# mixer.net
KiCad netlist of a schematic drawn in Altium Designer
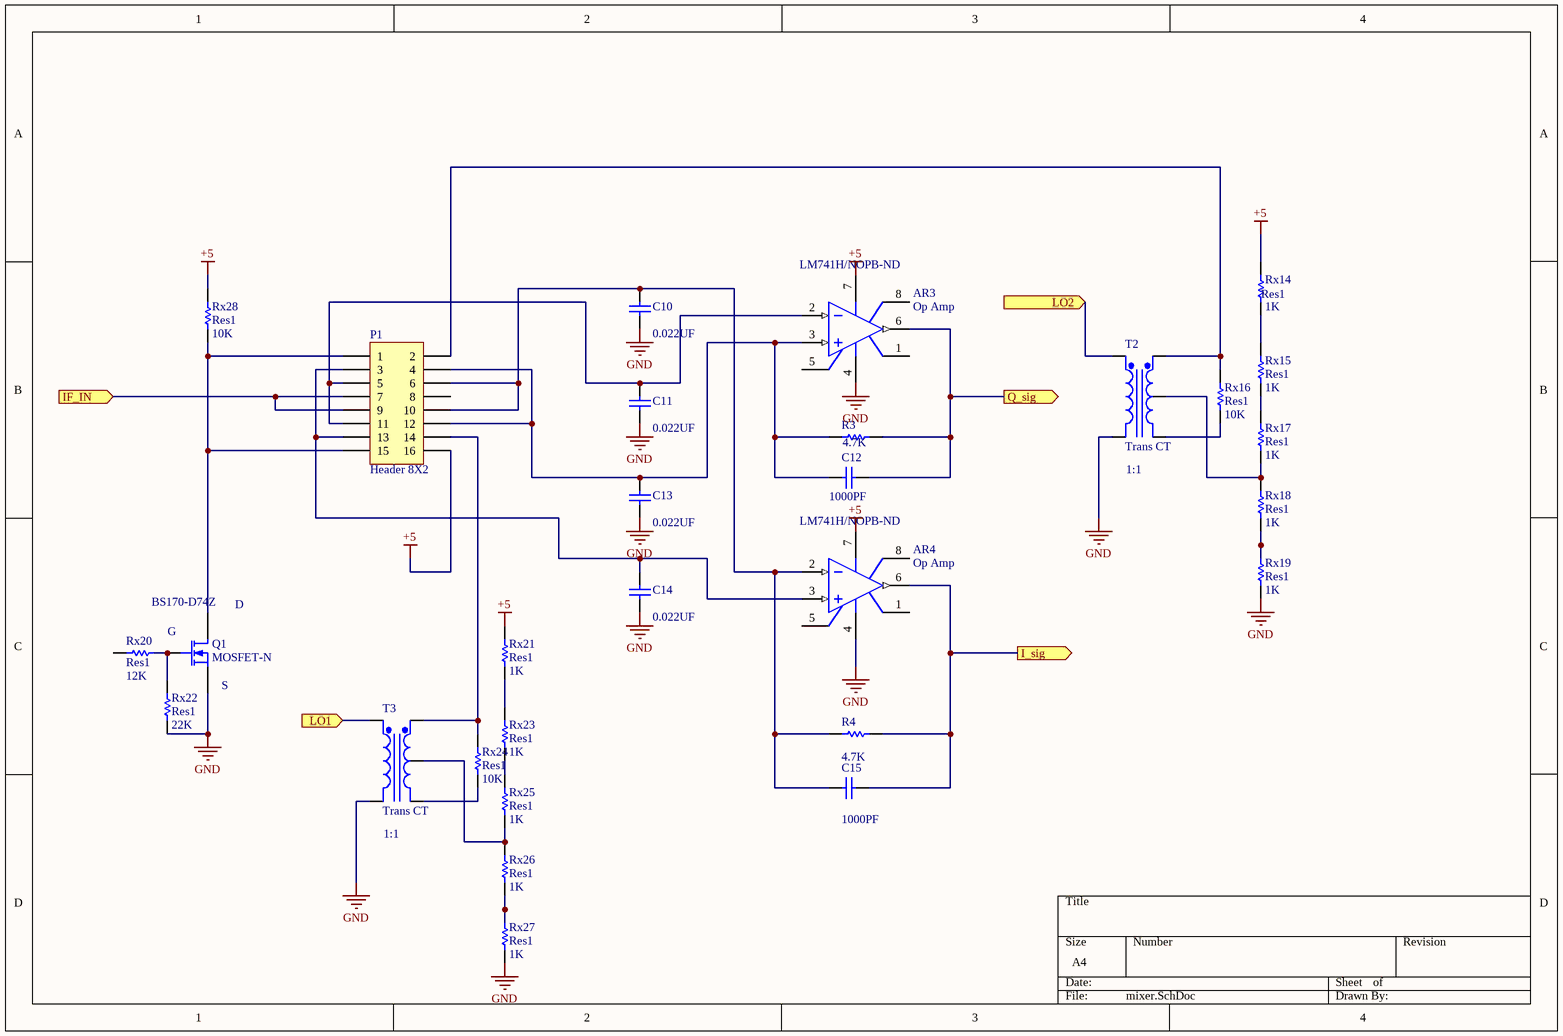
[diagram p0: mixer.SchDoc]

(export (version "E")
  (design (tool "Eeschema 10.0.6"))
  (components
    (comp (ref "AR3")
      (value "Op Amp")
      (footprint "H-08A")
      (description "FET Operational Amplifier")
      (fields
        (field (name "SUPPLIER PART NUMBER 1") "LM741H/NOPB-ND")
        (field (name "PUBLISHER") "Altium Limited")
      )
      (libsource (lib "Miscellaneous Devices") (part "Op Amp"))
    )
    (comp (ref "AR4")
      (value "Op Amp")
      (footprint "H-08A")
      (description "FET Operational Amplifier")
      (fields
        (field (name "SUPPLIER PART NUMBER 1") "LM741H/NOPB-ND")
        (field (name "PUBLISHER") "Altium Limited")
      )
      (libsource (lib "Miscellaneous Devices") (part "Op Amp"))
    )
    (comp (ref "C10")
      (value "0.022UF")
      (footprint "RADIAL-0.1")
      (description "Capacitor")
      (fields
        (field (name "MANUFACTURER PART NUMBER") "C315C223K5R5TA7303")
        (field (name "PUBLISHER") "Altium Limited")
      )
      (libsource (lib "ECE295-Capacitors-TH") (part "CAP CER 0.022UF 50V X7R RADIAL"))
    )
    (comp (ref "C11")
      (value "0.022UF")
      (footprint "RADIAL-0.1")
      (description "Capacitor")
      (fields
        (field (name "MANUFACTURER PART NUMBER") "C315C223K5R5TA7303")
        (field (name "PUBLISHER") "Altium Limited")
      )
      (libsource (lib "ECE295-Capacitors-TH") (part "CAP CER 0.022UF 50V X7R RADIAL"))
    )
    (comp (ref "C12")
      (value "1000PF")
      (footprint "RADIAL-0.1")
      (description "Capacitor")
      (fields
        (field (name "MANUFACTURER PART NUMBER") "C315C102M5U5TA")
        (field (name "Comment") "Cap")
        (field (name "PUBLISHER") "Altium Limited")
      )
      (libsource (lib "ECE295-Capacitors-TH") (part "CAP CER 1000PF 50V Z5U RADIAL"))
    )
    (comp (ref "C13")
      (value "0.022UF")
      (footprint "RADIAL-0.1")
      (description "Capacitor")
      (fields
        (field (name "MANUFACTURER PART NUMBER") "C315C223K5R5TA7303")
        (field (name "Comment") "Cap")
        (field (name "PUBLISHER") "Altium Limited")
      )
      (libsource (lib "ECE295-Capacitors-TH") (part "CAP CER 0.022UF 50V X7R RADIAL"))
    )
    (comp (ref "C14")
      (value "0.022UF")
      (footprint "RADIAL-0.1")
      (description "Capacitor")
      (fields
        (field (name "MANUFACTURER PART NUMBER") "C315C223K5R5TA7303")
        (field (name "Comment") "Cap")
        (field (name "PUBLISHER") "Altium Limited")
      )
      (libsource (lib "ECE295-Capacitors-TH") (part "CAP CER 0.022UF 50V X7R RADIAL"))
    )
    (comp (ref "C15")
      (value "1000PF")
      (footprint "RADIAL-0.1")
      (description "Capacitor")
      (fields
        (field (name "MANUFACTURER PART NUMBER") "C315C102M5U5TA")
        (field (name "Comment") "Cap")
        (field (name "PUBLISHER") "Altium Limited")
      )
      (libsource (lib "ECE295-Capacitors-TH") (part "CAP CER 1000PF 50V Z5U RADIAL"))
    )
    (comp (ref "P1")
      (value "Header 8X2")
      (footprint "HDR2X8")
      (description "Header, 8-Pin, Dual row")
      (fields (field (name "PUBLISHER") "Altium Limited"))
      (libsource (lib "Miscellaneous Connectors") (part "Header 8X2"))
    )
    (comp (ref "Q1")
      (value "MOSFET-N")
      (footprint "E3")
      (description "N-Channel MOSFET")
      (fields
        (field (name "SUPPLIER PART NUMBER 1") "BS170-D74Z")
        (field (name "PUBLISHER") "Altium Limited")
      )
      (libsource (lib "Miscellaneous Devices") (part "MOSFET-N"))
    )
    (comp (ref "R3")
      (value "4.7K")
      (footprint "AXIAL-0.1-RES")
      (description "Resistor")
      (fields
        (field (name "MANUFACTURER PART NUMBER") "CFR-25JB-52-4K7")
        (field (name "TOLERANCE") "0.05")
        (field (name "PUBLISHER") "Altium Limited")
      )
      (libsource (lib "ECE295-Resistors-TH") (part "RES 4.7K OHM 5% 1/4W AXIAL"))
    )
    (comp (ref "R4")
      (value "4.7K")
      (footprint "AXIAL-0.1-RES")
      (description "Resistor")
      (fields
        (field (name "MANUFACTURER PART NUMBER") "CFR-25JB-52-4K7")
        (field (name "TOLERANCE") "0.05")
        (field (name "PUBLISHER") "Altium Limited")
      )
      (libsource (lib "ECE295-Resistors-TH") (part "RES 4.7K OHM 5% 1/4W AXIAL"))
    )
    (comp (ref "Rx14")
      (value "Res1")
      (footprint "AXIAL-0.1-RES")
      (description "Resistor")
      (fields
        (field (name "MANUFACTURER PART NUMBER") "CFR-25JB-52-1K")
        (field (name "TOLERANCE") "0.05")
        (field (name "ALTIUM_VALUE") "1K")
        (field (name "PUBLISHER") "Altium Limited")
      )
      (libsource (lib "ECE295-Resistors-TH") (part "RES 1K OHM 5% 1/4W AXIAL"))
    )
    (comp (ref "Rx15")
      (value "Res1")
      (footprint "AXIAL-0.1-RES")
      (description "Resistor")
      (fields
        (field (name "MANUFACTURER PART NUMBER") "CFR-25JB-52-1K")
        (field (name "TOLERANCE") "0.05")
        (field (name "ALTIUM_VALUE") "1K")
        (field (name "PUBLISHER") "Altium Limited")
      )
      (libsource (lib "ECE295-Resistors-TH") (part "RES 1K OHM 5% 1/4W AXIAL"))
    )
    (comp (ref "Rx16")
      (value "Res1")
      (footprint "AXIAL-0.1-RES")
      (description "Resistor")
      (fields
        (field (name "ALTIUM_VALUE") "10K")
        (field (name "MANUFACTURER PART NUMBER") "CFR-25JB-52-10K")
        (field (name "TOLERANCE") "0.05")
        (field (name "PUBLISHER") "Altium Limited")
      )
      (libsource (lib "ECE295-Resistors-TH") (part "RES 10K OHM 5% 1/4W AXIAL"))
    )
    (comp (ref "Rx17")
      (value "Res1")
      (footprint "AXIAL-0.1-RES")
      (description "Resistor")
      (fields
        (field (name "MANUFACTURER PART NUMBER") "CFR-25JB-52-1K")
        (field (name "TOLERANCE") "0.05")
        (field (name "ALTIUM_VALUE") "1K")
        (field (name "PUBLISHER") "Altium Limited")
      )
      (libsource (lib "ECE295-Resistors-TH") (part "RES 1K OHM 5% 1/4W AXIAL"))
    )
    (comp (ref "Rx18")
      (value "Res1")
      (footprint "AXIAL-0.1-RES")
      (description "Resistor")
      (fields
        (field (name "MANUFACTURER PART NUMBER") "CFR-25JB-52-1K")
        (field (name "TOLERANCE") "0.05")
        (field (name "ALTIUM_VALUE") "1K")
        (field (name "PUBLISHER") "Altium Limited")
      )
      (libsource (lib "ECE295-Resistors-TH") (part "RES 1K OHM 5% 1/4W AXIAL"))
    )
    (comp (ref "Rx19")
      (value "Res1")
      (footprint "AXIAL-0.1-RES")
      (description "Resistor")
      (fields
        (field (name "MANUFACTURER PART NUMBER") "CFR-25JB-52-1K")
        (field (name "TOLERANCE") "0.05")
        (field (name "ALTIUM_VALUE") "1K")
        (field (name "PUBLISHER") "Altium Limited")
      )
      (libsource (lib "ECE295-Resistors-TH") (part "RES 1K OHM 5% 1/4W AXIAL"))
    )
    (comp (ref "Rx20")
      (value "Res1")
      (footprint "AXIAL-0.1-RES")
      (description "Resistor")
      (fields
        (field (name "ALTIUM_VALUE") "12K")
        (field (name "MANUFACTURER PART NUMBER") "CFR-25JB-52-12K")
        (field (name "TOLERANCE") "0.05")
        (field (name "PUBLISHER") "Altium Limited")
      )
      (libsource (lib "ECE295-Resistors-TH") (part "RES 12K OHM 5% 1/4W AXIAL"))
    )
    (comp (ref "Rx21")
      (value "Res1")
      (footprint "AXIAL-0.1-RES")
      (description "Resistor")
      (fields
        (field (name "MANUFACTURER PART NUMBER") "CFR-25JB-52-1K")
        (field (name "TOLERANCE") "0.05")
        (field (name "ALTIUM_VALUE") "1K")
        (field (name "PUBLISHER") "Altium Limited")
      )
      (libsource (lib "ECE295-Resistors-TH") (part "RES 1K OHM 5% 1/4W AXIAL"))
    )
    (comp (ref "Rx22")
      (value "Res1")
      (footprint "AXIAL-0.1-RES")
      (description "Resistor")
      (fields
        (field (name "ALTIUM_VALUE") "22K")
        (field (name "MANUFACTURER PART NUMBER") "CFR-25JB-52-22K")
        (field (name "TOLERANCE") "0.05")
        (field (name "PUBLISHER") "Altium Limited")
      )
      (libsource (lib "ECE295-Resistors-TH") (part "RES 22K OHM 5% 1/4W AXIAL"))
    )
    (comp (ref "Rx23")
      (value "Res1")
      (footprint "AXIAL-0.1-RES")
      (description "Resistor")
      (fields
        (field (name "MANUFACTURER PART NUMBER") "CFR-25JB-52-1K")
        (field (name "TOLERANCE") "0.05")
        (field (name "ALTIUM_VALUE") "1K")
        (field (name "PUBLISHER") "Altium Limited")
      )
      (libsource (lib "ECE295-Resistors-TH") (part "RES 1K OHM 5% 1/4W AXIAL"))
    )
    (comp (ref "Rx24")
      (value "Res1")
      (footprint "AXIAL-0.1-RES")
      (description "Resistor")
      (fields
        (field (name "ALTIUM_VALUE") "10K")
        (field (name "MANUFACTURER PART NUMBER") "CFR-25JB-52-10K")
        (field (name "TOLERANCE") "0.05")
        (field (name "PUBLISHER") "Altium Limited")
      )
      (libsource (lib "ECE295-Resistors-TH") (part "RES 10K OHM 5% 1/4W AXIAL"))
    )
    (comp (ref "Rx25")
      (value "Res1")
      (footprint "AXIAL-0.1-RES")
      (description "Resistor")
      (fields
        (field (name "MANUFACTURER PART NUMBER") "CFR-25JB-52-1K")
        (field (name "TOLERANCE") "0.05")
        (field (name "ALTIUM_VALUE") "1K")
        (field (name "PUBLISHER") "Altium Limited")
      )
      (libsource (lib "ECE295-Resistors-TH") (part "RES 1K OHM 5% 1/4W AXIAL"))
    )
    (comp (ref "Rx26")
      (value "Res1")
      (footprint "AXIAL-0.1-RES")
      (description "Resistor")
      (fields
        (field (name "MANUFACTURER PART NUMBER") "CFR-25JB-52-1K")
        (field (name "TOLERANCE") "0.05")
        (field (name "ALTIUM_VALUE") "1K")
        (field (name "PUBLISHER") "Altium Limited")
      )
      (libsource (lib "ECE295-Resistors-TH") (part "RES 1K OHM 5% 1/4W AXIAL"))
    )
    (comp (ref "Rx27")
      (value "Res1")
      (footprint "AXIAL-0.1-RES")
      (description "Resistor")
      (fields
        (field (name "MANUFACTURER PART NUMBER") "CFR-25JB-52-1K")
        (field (name "TOLERANCE") "0.05")
        (field (name "ALTIUM_VALUE") "1K")
        (field (name "PUBLISHER") "Altium Limited")
      )
      (libsource (lib "ECE295-Resistors-TH") (part "RES 1K OHM 5% 1/4W AXIAL"))
    )
    (comp (ref "Rx28")
      (value "Res1")
      (footprint "AXIAL-0.1-RES")
      (description "Resistor")
      (fields
        (field (name "ALTIUM_VALUE") "10K")
        (field (name "MANUFACTURER PART NUMBER") "CFR-25JB-52-10K")
        (field (name "TOLERANCE") "0.05")
        (field (name "PUBLISHER") "Altium Limited")
      )
      (libsource (lib "ECE295-Resistors-TH") (part "RES 10K OHM 5% 1/4W AXIAL"))
    )
    (comp (ref "T2")
      (value "Trans CT")
      (footprint "BIFILAR-2402")
      (description "Center-Tapped Transformer (Coupled Inductor Model)")
      (fields (field (name "PUBLISHER") "Altium Limited"))
      (libsource (lib "ECE295-Other") (part "Centre-tapped transformer wound on a binocular core"))
    )
    (comp (ref "T3")
      (value "Trans CT")
      (footprint "BIFILAR-2402")
      (description "Center-Tapped Transformer (Coupled Inductor Model)")
      (fields (field (name "PUBLISHER") "Altium Limited"))
      (libsource (lib "ECE295-Other") (part "Centre-tapped transformer wound on a binocular core"))
    )
  )
  (nets
    (net (code "1") (name "+5") (class "Default")
      (node (ref "AR3") (pin "7") (pinfunction "V+_7") (pintype "power_in"))
      (node (ref "AR4") (pin "7") (pinfunction "V+_7") (pintype "power_in"))
      (node (ref "P1") (pin "16") (pinfunction "16_16") (pintype "passive"))
      (node (ref "Rx14") (pin "2") (pinfunction "2_2") (pintype "passive"))
      (node (ref "Rx21") (pin "2") (pinfunction "2_2") (pintype "passive"))
      (node (ref "Rx28") (pin "2") (pinfunction "2_2") (pintype "passive"))
    )
    (net (code "2") (name "/IF_IN") (class "Default")
      (node (ref "P1") (pin "7") (pinfunction "7_7") (pintype "passive"))
      (node (ref "P1") (pin "9") (pinfunction "9_9") (pintype "passive"))
    )
    (net (code "3") (name "/I_sig") (class "Default")
      (node (ref "AR4") (pin "6") (pinfunction "OUT_6") (pintype "output"))
      (node (ref "C15") (pin "2") (pinfunction "2_2") (pintype "passive"))
      (node (ref "R4") (pin "2") (pinfunction "2_2") (pintype "passive"))
    )
    (net (code "4") (name "/LO1") (class "Default")
      (node (ref "T3") (pin "4") (pinfunction "Pri+_4") (pintype "passive"))
    )
    (net (code "5") (name "/LO2") (class "Default")
      (node (ref "T2") (pin "4") (pinfunction "Pri+_4") (pintype "passive"))
    )
    (net (code "6") (name "/Q_sig") (class "Default")
      (node (ref "AR3") (pin "6") (pinfunction "OUT_6") (pintype "output"))
      (node (ref "C12") (pin "2") (pinfunction "2_2") (pintype "passive"))
      (node (ref "R3") (pin "2") (pinfunction "2_2") (pintype "passive"))
    )
    (net (code "7") (name "GND") (class "Default")
      (node (ref "AR3") (pin "4") (pinfunction "V-_4") (pintype "power_in"))
      (node (ref "AR4") (pin "4") (pinfunction "V-_4") (pintype "power_in"))
      (node (ref "C10") (pin "1") (pinfunction "1_1") (pintype "passive"))
      (node (ref "C11") (pin "1") (pinfunction "1_1") (pintype "passive"))
      (node (ref "C13") (pin "1") (pinfunction "1_1") (pintype "passive"))
      (node (ref "C14") (pin "1") (pinfunction "1_1") (pintype "passive"))
      (node (ref "Q1") (pin "3") (pinfunction "S_3") (pintype "passive"))
      (node (ref "Rx19") (pin "1") (pinfunction "1_1") (pintype "passive"))
      (node (ref "Rx22") (pin "1") (pinfunction "1_1") (pintype "passive"))
      (node (ref "Rx27") (pin "1") (pinfunction "1_1") (pintype "passive"))
      (node (ref "T2") (pin "5") (pinfunction "Pri-_5") (pintype "passive"))
      (node (ref "T3") (pin "5") (pinfunction "Pri-_5") (pintype "passive"))
    )
    (net (code "8") (name "Net-(AR3-IN+)") (class "Default")
      (node (ref "AR3") (pin "3") (pinfunction "IN+_3") (pintype "input"))
      (node (ref "C12") (pin "1") (pinfunction "1_1") (pintype "passive"))
      (node (ref "C13") (pin "2") (pinfunction "2_2") (pintype "passive"))
      (node (ref "P1") (pin "12") (pinfunction "12_12") (pintype "passive"))
      (node (ref "P1") (pin "4") (pinfunction "4_4") (pintype "passive"))
      (node (ref "R3") (pin "1") (pinfunction "1_1") (pintype "passive"))
    )
    (net (code "9") (name "Net-(AR3-IN-)") (class "Default")
      (node (ref "AR3") (pin "2") (pinfunction "IN-_2") (pintype "input"))
      (node (ref "C11") (pin "2") (pinfunction "2_2") (pintype "passive"))
      (node (ref "P1") (pin "11") (pinfunction "11_11") (pintype "passive"))
      (node (ref "P1") (pin "5") (pinfunction "5_5") (pintype "passive"))
    )
    (net (code "10") (name "Net-(AR4-IN+)") (class "Default")
      (node (ref "AR4") (pin "3") (pinfunction "IN+_3") (pintype "input"))
      (node (ref "C14") (pin "2") (pinfunction "2_2") (pintype "passive"))
      (node (ref "P1") (pin "13") (pinfunction "13_13") (pintype "passive"))
      (node (ref "P1") (pin "3") (pinfunction "3_3") (pintype "passive"))
    )
    (net (code "11") (name "Net-(AR4-IN-)") (class "Default")
      (node (ref "AR4") (pin "2") (pinfunction "IN-_2") (pintype "input"))
      (node (ref "C10") (pin "2") (pinfunction "2_2") (pintype "passive"))
      (node (ref "C15") (pin "1") (pinfunction "1_1") (pintype "passive"))
      (node (ref "P1") (pin "10") (pinfunction "10_10") (pintype "passive"))
      (node (ref "P1") (pin "6") (pinfunction "6_6") (pintype "passive"))
      (node (ref "R4") (pin "1") (pinfunction "1_1") (pintype "passive"))
    )
    (net (code "12") (name "Net-(Q1-D)") (class "Default")
      (node (ref "P1") (pin "1") (pinfunction "1_1") (pintype "passive"))
      (node (ref "P1") (pin "15") (pinfunction "15_15") (pintype "passive"))
      (node (ref "Q1") (pin "1") (pinfunction "D_1") (pintype "passive"))
      (node (ref "Rx28") (pin "1") (pinfunction "1_1") (pintype "passive"))
    )
    (net (code "13") (name "Net-(Q1-G)") (class "Default")
      (node (ref "Q1") (pin "2") (pinfunction "G_2") (pintype "passive"))
      (node (ref "Rx20") (pin "2") (pinfunction "2_2") (pintype "passive"))
      (node (ref "Rx22") (pin "2") (pinfunction "2_2") (pintype "passive"))
    )
    (net (code "14") (name "Net-(Rx14-Pad1)") (class "Default")
      (node (ref "Rx14") (pin "1") (pinfunction "1_1") (pintype "passive"))
      (node (ref "Rx15") (pin "2") (pinfunction "2_2") (pintype "passive"))
    )
    (net (code "15") (name "Net-(Rx15-Pad1)") (class "Default")
      (node (ref "Rx15") (pin "1") (pinfunction "1_1") (pintype "passive"))
      (node (ref "Rx17") (pin "2") (pinfunction "2_2") (pintype "passive"))
    )
    (net (code "16") (name "Net-(Rx18-Pad1)") (class "Default")
      (node (ref "Rx18") (pin "1") (pinfunction "1_1") (pintype "passive"))
      (node (ref "Rx19") (pin "2") (pinfunction "2_2") (pintype "passive"))
    )
    (net (code "17") (name "Net-(Rx21-Pad1)") (class "Default")
      (node (ref "Rx21") (pin "1") (pinfunction "1_1") (pintype "passive"))
      (node (ref "Rx23") (pin "2") (pinfunction "2_2") (pintype "passive"))
    )
    (net (code "18") (name "Net-(Rx23-Pad1)") (class "Default")
      (node (ref "Rx23") (pin "1") (pinfunction "1_1") (pintype "passive"))
      (node (ref "Rx25") (pin "2") (pinfunction "2_2") (pintype "passive"))
    )
    (net (code "19") (name "Net-(Rx26-Pad1)") (class "Default")
      (node (ref "Rx26") (pin "1") (pinfunction "1_1") (pintype "passive"))
      (node (ref "Rx27") (pin "2") (pinfunction "2_2") (pintype "passive"))
    )
    (net (code "20") (name "Net-(T2-Sec+)") (class "Default")
      (node (ref "P1") (pin "2") (pinfunction "2_2") (pintype "passive"))
      (node (ref "Rx16") (pin "2") (pinfunction "2_2") (pintype "passive"))
      (node (ref "T2") (pin "1") (pinfunction "Sec+_1") (pintype "passive"))
    )
    (net (code "21") (name "Net-(T2-Sec-)") (class "Default")
      (node (ref "Rx16") (pin "1") (pinfunction "1_1") (pintype "passive"))
      (node (ref "T2") (pin "3") (pinfunction "Sec-_3") (pintype "passive"))
    )
    (net (code "22") (name "Net-(T2-SecCT)") (class "Default")
      (node (ref "Rx17") (pin "1") (pinfunction "1_1") (pintype "passive"))
      (node (ref "Rx18") (pin "2") (pinfunction "2_2") (pintype "passive"))
      (node (ref "T2") (pin "2") (pinfunction "SecCT_2") (pintype "passive"))
    )
    (net (code "23") (name "Net-(T3-Sec+)") (class "Default")
      (node (ref "P1") (pin "14") (pinfunction "14_14") (pintype "passive"))
      (node (ref "Rx24") (pin "2") (pinfunction "2_2") (pintype "passive"))
      (node (ref "T3") (pin "1") (pinfunction "Sec+_1") (pintype "passive"))
    )
    (net (code "24") (name "Net-(T3-Sec-)") (class "Default")
      (node (ref "Rx24") (pin "1") (pinfunction "1_1") (pintype "passive"))
      (node (ref "T3") (pin "3") (pinfunction "Sec-_3") (pintype "passive"))
    )
    (net (code "25") (name "Net-(T3-SecCT)") (class "Default")
      (node (ref "Rx25") (pin "1") (pinfunction "1_1") (pintype "passive"))
      (node (ref "Rx26") (pin "2") (pinfunction "2_2") (pintype "passive"))
      (node (ref "T3") (pin "2") (pinfunction "SecCT_2") (pintype "passive"))
    )
    (net (code "26") (name "unconnected-(AR3-OS_NUL-Pad1)") (class "Default")
      (node (ref "AR3") (pin "1") (pinfunction "OS_NUL_1") (pintype "passive"))
    )
    (net (code "27") (name "unconnected-(AR3-OS_NUL-Pad5)") (class "Default")
      (node (ref "AR3") (pin "5") (pinfunction "OS_NUL_5") (pintype "passive"))
    )
    (net (code "28") (name "unconnected-(AR3-TAB-Pad8)") (class "Default")
      (node (ref "AR3") (pin "8") (pinfunction "TAB_8") (pintype "passive"))
    )
    (net (code "29") (name "unconnected-(AR4-OS_NUL-Pad1)") (class "Default")
      (node (ref "AR4") (pin "1") (pinfunction "OS_NUL_1") (pintype "passive"))
    )
    (net (code "30") (name "unconnected-(AR4-OS_NUL-Pad5)") (class "Default")
      (node (ref "AR4") (pin "5") (pinfunction "OS_NUL_5") (pintype "passive"))
    )
    (net (code "31") (name "unconnected-(AR4-TAB-Pad8)") (class "Default")
      (node (ref "AR4") (pin "8") (pinfunction "TAB_8") (pintype "passive"))
    )
    (net (code "32") (name "unconnected-(P1-Pad8)") (class "Default")
      (node (ref "P1") (pin "8") (pinfunction "8_8") (pintype "passive"))
    )
    (net (code "33") (name "unconnected-(Rx20-Pad1)") (class "Default")
      (node (ref "Rx20") (pin "1") (pinfunction "1_1") (pintype "passive"))
    )
  )
)
